# 01-POWER.net
KiCad netlist of a schematic drawn in Altium Designer
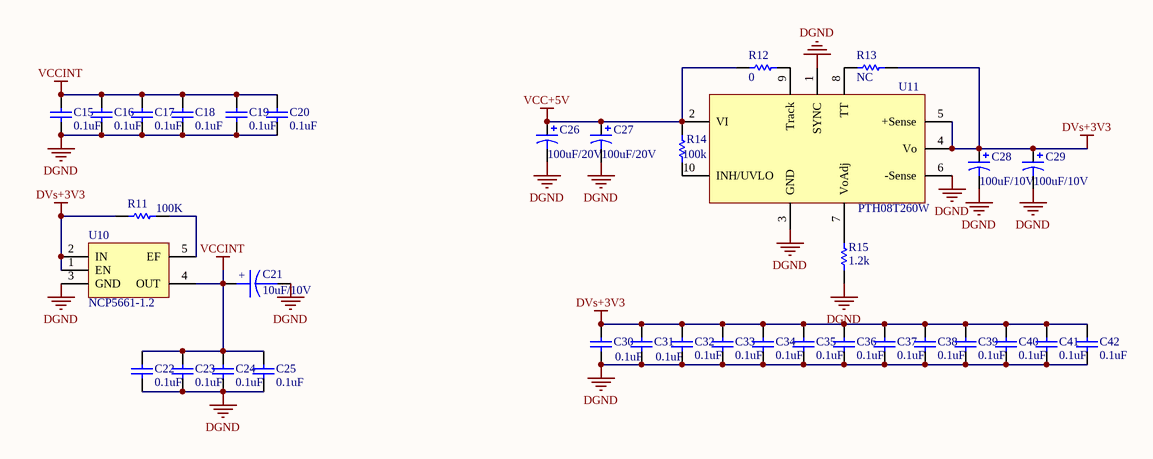
[diagram p0: 01-POWER.SchDoc]

(export (version "E")
  (design (tool "Eeschema 10.0.6"))
  (components
    (comp (ref "C15")
      (value "0.1uF")
      (footprint "0805-X")
      (description "Capacitor")
      (fields (field (name "PUBLISHER") "Altium Limited"))
      (libsource (lib "*") (part "Cap"))
    )
    (comp (ref "C16")
      (value "0.1uF")
      (footprint "0805-X")
      (description "Capacitor")
      (fields (field (name "PUBLISHER") "Altium Limited"))
      (libsource (lib "*") (part "Cap"))
    )
    (comp (ref "C17")
      (value "0.1uF")
      (footprint "0805-X")
      (description "Capacitor")
      (fields (field (name "PUBLISHER") "Altium Limited"))
      (libsource (lib "*") (part "Cap"))
    )
    (comp (ref "C18")
      (value "0.1uF")
      (footprint "0805-X")
      (description "Capacitor")
      (fields (field (name "PUBLISHER") "Altium Limited"))
      (libsource (lib "*") (part "Cap"))
    )
    (comp (ref "C19")
      (value "0.1uF")
      (footprint "0805-X")
      (description "Capacitor")
      (fields (field (name "PUBLISHER") "Altium Limited"))
      (libsource (lib "*") (part "Cap"))
    )
    (comp (ref "C20")
      (value "0.1uF")
      (footprint "0805-X")
      (description "Capacitor")
      (fields (field (name "PUBLISHER") "Altium Limited"))
      (libsource (lib "*") (part "Cap"))
    )
    (comp (ref "C21")
      (value "10uF/10V")
      (footprint "CC3225-1210")
      (description "Capacitor")
      (libsource (lib "*") (part "CAPACITOR POL"))
    )
    (comp (ref "C22")
      (value "0.1uF")
      (footprint "0805-X")
      (description "Capacitor (Semiconductor SIM Model)")
      (fields (field (name "PUBLISHER") "Altium Limited"))
      (libsource (lib "Miscellaneous Devices") (part "Cap Semi"))
    )
    (comp (ref "C23")
      (value "0.1uF")
      (footprint "0805-X")
      (description "Capacitor (Semiconductor SIM Model)")
      (fields (field (name "PUBLISHER") "Altium Limited"))
      (libsource (lib "Miscellaneous Devices") (part "Cap Semi"))
    )
    (comp (ref "C24")
      (value "0.1uF")
      (footprint "0805-X")
      (description "Capacitor (Semiconductor SIM Model)")
      (fields (field (name "PUBLISHER") "Altium Limited"))
      (libsource (lib "Miscellaneous Devices") (part "Cap Semi"))
    )
    (comp (ref "C25")
      (value "0.1uF")
      (footprint "0805-X")
      (description "Capacitor (Semiconductor SIM Model)")
      (fields (field (name "PUBLISHER") "Altium Limited"))
      (libsource (lib "Miscellaneous Devices") (part "Cap Semi"))
    )
    (comp (ref "C26")
      (value "100uF/20V")
      (footprint "CC7343")
      (description "钽电容,25V")
      (fields (field (name "PUBLISHER") "Altium Limited"))
      (libsource (lib "Miscellaneous Devices") (part "Cap Pol1"))
    )
    (comp (ref "C27")
      (value "100uF/20V")
      (footprint "CC7343")
      (description "钽电容,25V")
      (fields (field (name "PUBLISHER") "Altium Limited"))
      (libsource (lib "Miscellaneous Devices") (part "Cap Pol1"))
    )
    (comp (ref "C28")
      (value "100uF/10V")
      (footprint "CC7343")
      (description "10V, X7R")
      (fields (field (name "PUBLISHER") "Altium Limited"))
      (libsource (lib "Miscellaneous Devices") (part "Cap Pol1"))
    )
    (comp (ref "C29")
      (value "100uF/10V")
      (footprint "CC7343")
      (description "10V, X7R")
      (fields (field (name "PUBLISHER") "Altium Limited"))
      (libsource (lib "Miscellaneous Devices") (part "Cap Pol1"))
    )
    (comp (ref "C30")
      (value "0.1uF")
      (footprint "0805-X")
      (description "Capacitor (Semiconductor SIM Model)")
      (fields (field (name "PUBLISHER") "Altium Limited"))
      (libsource (lib "Miscellaneous Devices") (part "Cap Semi"))
    )
    (comp (ref "C31")
      (value "0.1uF")
      (footprint "0805-X")
      (description "Capacitor (Semiconductor SIM Model)")
      (fields (field (name "PUBLISHER") "Altium Limited"))
      (libsource (lib "Miscellaneous Devices") (part "Cap Semi"))
    )
    (comp (ref "C32")
      (value "0.1uF")
      (footprint "0805-X")
      (description "Capacitor (Semiconductor SIM Model)")
      (fields (field (name "PUBLISHER") "Altium Limited"))
      (libsource (lib "Miscellaneous Devices") (part "Cap Semi"))
    )
    (comp (ref "C33")
      (value "0.1uF")
      (footprint "0805-X")
      (description "Capacitor (Semiconductor SIM Model)")
      (fields (field (name "PUBLISHER") "Altium Limited"))
      (libsource (lib "Miscellaneous Devices") (part "Cap Semi"))
    )
    (comp (ref "C34")
      (value "0.1uF")
      (footprint "0805-X")
      (description "Capacitor (Semiconductor SIM Model)")
      (fields (field (name "PUBLISHER") "Altium Limited"))
      (libsource (lib "Miscellaneous Devices") (part "Cap Semi"))
    )
    (comp (ref "C35")
      (value "0.1uF")
      (footprint "0805-X")
      (description "Capacitor (Semiconductor SIM Model)")
      (fields (field (name "PUBLISHER") "Altium Limited"))
      (libsource (lib "Miscellaneous Devices") (part "Cap Semi"))
    )
    (comp (ref "C36")
      (value "0.1uF")
      (footprint "0805-X")
      (description "Capacitor (Semiconductor SIM Model)")
      (fields (field (name "PUBLISHER") "Altium Limited"))
      (libsource (lib "Miscellaneous Devices") (part "Cap Semi"))
    )
    (comp (ref "C37")
      (value "0.1uF")
      (footprint "0805-X")
      (description "Capacitor (Semiconductor SIM Model)")
      (fields (field (name "PUBLISHER") "Altium Limited"))
      (libsource (lib "Miscellaneous Devices") (part "Cap Semi"))
    )
    (comp (ref "C38")
      (value "0.1uF")
      (footprint "0805-X")
      (description "Capacitor (Semiconductor SIM Model)")
      (fields (field (name "PUBLISHER") "Altium Limited"))
      (libsource (lib "Miscellaneous Devices") (part "Cap Semi"))
    )
    (comp (ref "C39")
      (value "0.1uF")
      (footprint "0805-X")
      (description "Capacitor (Semiconductor SIM Model)")
      (fields (field (name "PUBLISHER") "Altium Limited"))
      (libsource (lib "Miscellaneous Devices") (part "Cap Semi"))
    )
    (comp (ref "C40")
      (value "0.1uF")
      (footprint "0805-X")
      (description "Capacitor (Semiconductor SIM Model)")
      (fields (field (name "PUBLISHER") "Altium Limited"))
      (libsource (lib "Miscellaneous Devices") (part "Cap Semi"))
    )
    (comp (ref "C41")
      (value "0.1uF")
      (footprint "0805-X")
      (description "Capacitor (Semiconductor SIM Model)")
      (fields (field (name "PUBLISHER") "Altium Limited"))
      (libsource (lib "Miscellaneous Devices") (part "Cap Semi"))
    )
    (comp (ref "C42")
      (value "0.1uF")
      (footprint "0805-X")
      (description "Capacitor (Semiconductor SIM Model)")
      (fields (field (name "PUBLISHER") "Altium Limited"))
      (libsource (lib "Miscellaneous Devices") (part "Cap Semi"))
    )
    (comp (ref "R11")
      (value "100K")
      (footprint "0805")
      (description "Semiconductor Resistor")
      (fields (field (name "PUBLISHER") "Altium Limited"))
      (libsource (lib "Miscellaneous Devices") (part "Res Semi"))
    )
    (comp (ref "R12")
      (value "0")
      (footprint "CR2012-0805")
      (description "Resistor")
      (fields (field (name "PUBLISHER") "Altium Limited"))
      (libsource (lib "Miscellaneous Devices") (part "Res1"))
    )
    (comp (ref "R13")
      (value "NC")
      (footprint "CR2012-0805")
      (description "Resistor")
      (fields (field (name "PUBLISHER") "Altium Limited"))
      (libsource (lib "Miscellaneous Devices") (part "Res1"))
    )
    (comp (ref "R14")
      (value "100k")
      (footprint "CR2012-0805")
      (description "Resistor")
      (fields (field (name "PUBLISHER") "Altium Limited"))
      (libsource (lib "Miscellaneous Devices") (part "Res1"))
    )
    (comp (ref "R15")
      (value "1.2k")
      (footprint "CR2012-0805")
      (description "Resistor")
      (fields (field (name "PUBLISHER") "Altium Limited"))
      (libsource (lib "Miscellaneous Devices") (part "Res1"))
    )
    (comp (ref "U10") (value "NCP5661-1.2") (footprint "DPAK5") (libsource (lib "*") (part "NCP5661")))
    (comp (ref "U11")
      (value "PTH08T260W")
      (footprint "TI_R-PDSS-T10")
      (description "TI电源模块")
      (libsource (lib "IC") (part "PTH08T230W"))
    )
  )
  (nets
    (net (code "1") (name "DGND") (class "Default")
      (node (ref "C15") (pin "1") (pinfunction "1_1") (pintype "passive"))
      (node (ref "C16") (pin "1") (pinfunction "1_1") (pintype "passive"))
      (node (ref "C17") (pin "1") (pinfunction "1_1") (pintype "passive"))
      (node (ref "C18") (pin "1") (pinfunction "1_1") (pintype "passive"))
      (node (ref "C19") (pin "1") (pinfunction "1_1") (pintype "passive"))
      (node (ref "C20") (pin "1") (pinfunction "1_1") (pintype "passive"))
      (node (ref "C21") (pin "2") (pinfunction "2_2") (pintype "passive"))
      (node (ref "C22") (pin "1") (pinfunction "1_1") (pintype "passive"))
      (node (ref "C23") (pin "1") (pinfunction "1_1") (pintype "passive"))
      (node (ref "C24") (pin "1") (pinfunction "1_1") (pintype "passive"))
      (node (ref "C25") (pin "1") (pinfunction "1_1") (pintype "passive"))
      (node (ref "C26") (pin "2") (pinfunction "2_2") (pintype "passive"))
      (node (ref "C27") (pin "2") (pinfunction "2_2") (pintype "passive"))
      (node (ref "C28") (pin "2") (pinfunction "2_2") (pintype "passive"))
      (node (ref "C29") (pin "2") (pinfunction "2_2") (pintype "passive"))
      (node (ref "C30") (pin "1") (pinfunction "1_1") (pintype "passive"))
      (node (ref "C31") (pin "1") (pinfunction "1_1") (pintype "passive"))
      (node (ref "C32") (pin "1") (pinfunction "1_1") (pintype "passive"))
      (node (ref "C33") (pin "1") (pinfunction "1_1") (pintype "passive"))
      (node (ref "C34") (pin "1") (pinfunction "1_1") (pintype "passive"))
      (node (ref "C35") (pin "1") (pinfunction "1_1") (pintype "passive"))
      (node (ref "C36") (pin "1") (pinfunction "1_1") (pintype "passive"))
      (node (ref "C37") (pin "1") (pinfunction "1_1") (pintype "passive"))
      (node (ref "C38") (pin "1") (pinfunction "1_1") (pintype "passive"))
      (node (ref "C39") (pin "1") (pinfunction "1_1") (pintype "passive"))
      (node (ref "C40") (pin "1") (pinfunction "1_1") (pintype "passive"))
      (node (ref "C41") (pin "1") (pinfunction "1_1") (pintype "passive"))
      (node (ref "C42") (pin "1") (pinfunction "1_1") (pintype "passive"))
      (node (ref "R15") (pin "1") (pinfunction "1_1") (pintype "passive"))
      (node (ref "U10") (pin "3") (pinfunction "GND_3") (pintype "power_in"))
      (node (ref "U11") (pin "1") (pinfunction "SYNC_1") (pintype "passive"))
      (node (ref "U11") (pin "3") (pinfunction "GND_3") (pintype "power_in"))
      (node (ref "U11") (pin "6") (pinfunction "-Sense_6") (pintype "passive"))
    )
    (net (code "2") (name "DVs+3V3") (class "Default")
      (node (ref "C28") (pin "1") (pinfunction "1_1") (pintype "passive"))
      (node (ref "C29") (pin "1") (pinfunction "1_1") (pintype "passive"))
      (node (ref "C30") (pin "2") (pinfunction "2_2") (pintype "passive"))
      (node (ref "C31") (pin "2") (pinfunction "2_2") (pintype "passive"))
      (node (ref "C32") (pin "2") (pinfunction "2_2") (pintype "passive"))
      (node (ref "C33") (pin "2") (pinfunction "2_2") (pintype "passive"))
      (node (ref "C34") (pin "2") (pinfunction "2_2") (pintype "passive"))
      (node (ref "C35") (pin "2") (pinfunction "2_2") (pintype "passive"))
      (node (ref "C36") (pin "2") (pinfunction "2_2") (pintype "passive"))
      (node (ref "C37") (pin "2") (pinfunction "2_2") (pintype "passive"))
      (node (ref "C38") (pin "2") (pinfunction "2_2") (pintype "passive"))
      (node (ref "C39") (pin "2") (pinfunction "2_2") (pintype "passive"))
      (node (ref "C40") (pin "2") (pinfunction "2_2") (pintype "passive"))
      (node (ref "C41") (pin "2") (pinfunction "2_2") (pintype "passive"))
      (node (ref "C42") (pin "2") (pinfunction "2_2") (pintype "passive"))
      (node (ref "R11") (pin "1") (pinfunction "1_1") (pintype "passive"))
      (node (ref "R13") (pin "1") (pinfunction "1_1") (pintype "passive"))
      (node (ref "U10") (pin "1") (pinfunction "EN_1") (pintype "power_in"))
      (node (ref "U10") (pin "2") (pinfunction "IN_2") (pintype "power_in"))
      (node (ref "U11") (pin "4") (pinfunction "Vo_4") (pintype "power_in"))
      (node (ref "U11") (pin "5") (pinfunction "+Sense_5") (pintype "passive"))
    )
    (net (code "3") (name "Net-(U10-EF)") (class "Default")
      (node (ref "R11") (pin "2") (pinfunction "2_2") (pintype "passive"))
      (node (ref "U10") (pin "5") (pinfunction "EF_5") (pintype "power_in"))
    )
    (net (code "4") (name "Net-(U11-INH{slash}UVLO)") (class "Default")
      (node (ref "R14") (pin "1") (pinfunction "1_1") (pintype "passive"))
      (node (ref "U11") (pin "10") (pinfunction "INH/UVLO_10") (pintype "passive"))
    )
    (net (code "5") (name "Net-(U11-TT)") (class "Default")
      (node (ref "R13") (pin "2") (pinfunction "2_2") (pintype "passive"))
      (node (ref "U11") (pin "8") (pinfunction "TT_8") (pintype "passive"))
    )
    (net (code "6") (name "Net-(U11-Track)") (class "Default")
      (node (ref "R12") (pin "1") (pinfunction "1_1") (pintype "passive"))
      (node (ref "U11") (pin "9") (pinfunction "Track_9") (pintype "passive"))
    )
    (net (code "7") (name "Net-(U11-VoAdj)") (class "Default")
      (node (ref "R15") (pin "2") (pinfunction "2_2") (pintype "passive"))
      (node (ref "U11") (pin "7") (pinfunction "VoAdj_7") (pintype "power_in"))
    )
    (net (code "8") (name "VCC+5V") (class "Default")
      (node (ref "C26") (pin "1") (pinfunction "1_1") (pintype "passive"))
      (node (ref "C27") (pin "1") (pinfunction "1_1") (pintype "passive"))
      (node (ref "R12") (pin "2") (pinfunction "2_2") (pintype "passive"))
      (node (ref "R14") (pin "2") (pinfunction "2_2") (pintype "passive"))
      (node (ref "U11") (pin "2") (pinfunction "VI_2") (pintype "power_in"))
    )
    (net (code "9") (name "VCCINT") (class "Default")
      (node (ref "C15") (pin "2") (pinfunction "2_2") (pintype "passive"))
      (node (ref "C16") (pin "2") (pinfunction "2_2") (pintype "passive"))
      (node (ref "C17") (pin "2") (pinfunction "2_2") (pintype "passive"))
      (node (ref "C18") (pin "2") (pinfunction "2_2") (pintype "passive"))
      (node (ref "C19") (pin "2") (pinfunction "2_2") (pintype "passive"))
      (node (ref "C20") (pin "2") (pinfunction "2_2") (pintype "passive"))
      (node (ref "C21") (pin "1") (pinfunction "1_1") (pintype "passive"))
      (node (ref "C22") (pin "2") (pinfunction "2_2") (pintype "passive"))
      (node (ref "C23") (pin "2") (pinfunction "2_2") (pintype "passive"))
      (node (ref "C24") (pin "2") (pinfunction "2_2") (pintype "passive"))
      (node (ref "C25") (pin "2") (pinfunction "2_2") (pintype "passive"))
      (node (ref "U10") (pin "4") (pinfunction "OUT_4") (pintype "power_in"))
    )
  )
)
